# LCD_Sheet.net
KiCad netlist of a schematic drawn in Altium Designer
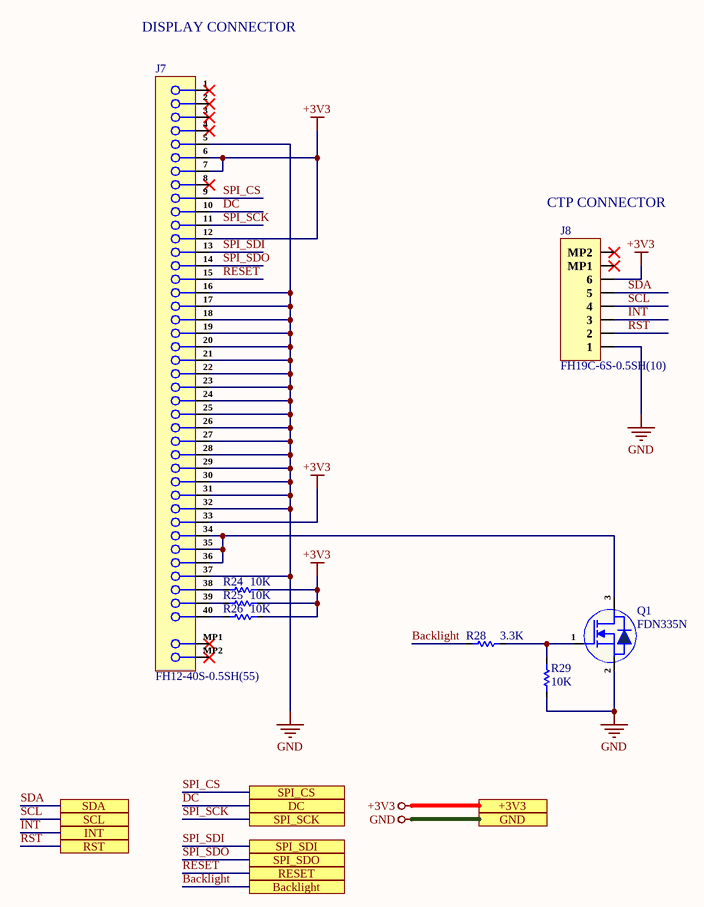
[diagram p0: LCD_Sheet.SchDoc]

(export (version "E")
  (design (tool "Eeschema 10.0.6"))
  (components
    (comp (ref "J7")
      (value "FH12-40S-0.5SH(55)")
      (footprint "FH12-40S-0.5SH(55)")
      (description "CONN FFC BOTTOM 40POS 0.50MM R/A")
      (fields (field (name "MANUFACTURER") "Hirose") (field (name "LCSC PART NUMBER") "C202114"))
      (libsource (lib "DigitalAzanClock") (part "FH12-40S-0.5SH(55)"))
    )
    (comp (ref "J8")
      (value "FH19C-6S-0.5SH(10)")
      (footprint "FH19C-6S-0.5SH(10)_")
      (description "CONN FFC BOTTOM 6POS 0.50MM R/A")
      (fields (field (name "MANUFACTURER") "Hirose") (field (name "LCSC PART NUMBER") "C424651"))
      (libsource (lib "DigitalAzanClock") (part "FH19C-6S-0.5SH(10)"))
    )
    (comp (ref "Q1")
      (value "FDN335N")
      (footprint "SOT-23")
      (description "SOT-23 MOSFETs ROHS")
      (fields (field (name "MANUFACTURER") "TECH PUBLIC") (field (name "LCSC PART NUMBER") "C5123904"))
      (libsource (lib "DigitalAzanClock") (part "FDN335N"))
    )
    (comp (ref "R24")
      (value "10K")
      (footprint "Res-0603")
      (description "RES SMD 10K OHM 0.1% 1/10W 0603")
      (fields
        (field (name "MANUFACTURER") "Yageo")
        (field (name "MANUFACTURER PART NUMBER") "RT0603BRD0710KL")
      )
      (libsource (lib "DigitalAzanClock") (part "RT0603BRD0710KL"))
    )
    (comp (ref "R25")
      (value "10K")
      (footprint "Res-0603")
      (description "RES SMD 10K OHM 0.1% 1/10W 0603")
      (fields
        (field (name "MANUFACTURER") "Yageo")
        (field (name "MANUFACTURER PART NUMBER") "RT0603BRD0710KL")
      )
      (libsource (lib "DigitalAzanClock") (part "RT0603BRD0710KL"))
    )
    (comp (ref "R26")
      (value "10K")
      (footprint "Res-0603")
      (description "RES SMD 10K OHM 0.1% 1/10W 0603")
      (fields
        (field (name "MANUFACTURER") "Yageo")
        (field (name "MANUFACTURER PART NUMBER") "RT0603BRD0710KL")
      )
      (libsource (lib "DigitalAzanClock") (part "RT0603BRD0710KL"))
    )
    (comp (ref "R28")
      (value "3.3K")
      (footprint "Res-0603")
      (description "RES SMD 3.3K OHM 1% 1/10W 0603")
      (fields
        (field (name "MANUFACTURER") "Yageo Phycomp")
        (field (name "MANUFACTURER PART NUMBER") "RC0603FR-073K3L")
      )
      (libsource (lib "DigitalAzanClock") (part "RC0603FR-073K3L"))
    )
    (comp (ref "R29")
      (value "10K")
      (footprint "Res-0603")
      (description "RES SMD 10K OHM 0.1% 1/10W 0603")
      (fields
        (field (name "MANUFACTURER") "Yageo")
        (field (name "MANUFACTURER PART NUMBER") "RT0603BRD0710KL")
      )
      (libsource (lib "DigitalAzanClock") (part "RT0603BRD0710KL"))
    )
  )
  (nets
    (net (code "1") (name "+3V3") (class "Default")
      (node (ref "J7") (pin "12") (pinfunction "12_12") (pintype "passive"))
      (node (ref "J7") (pin "33") (pinfunction "33_33") (pintype "passive"))
      (node (ref "J7") (pin "6") (pinfunction "6_6") (pintype "passive"))
      (node (ref "J7") (pin "7") (pinfunction "7_7") (pintype "passive"))
      (node (ref "J8") (pin "6") (pinfunction "6_6") (pintype "passive"))
      (node (ref "R24") (pin "2") (pinfunction "2_2") (pintype "passive"))
      (node (ref "R25") (pin "2") (pinfunction "2_2") (pintype "passive"))
      (node (ref "R26") (pin "2") (pinfunction "2_2") (pintype "passive"))
    )
    (net (code "2") (name "/Backlight") (class "Default")
      (node (ref "R28") (pin "1") (pinfunction "1_1") (pintype "passive"))
    )
    (net (code "3") (name "/DC") (class "Default")
      (node (ref "J7") (pin "10") (pinfunction "10_10") (pintype "passive"))
    )
    (net (code "4") (name "/INT") (class "Default")
      (node (ref "J8") (pin "3") (pinfunction "3_3") (pintype "passive"))
    )
    (net (code "5") (name "/RESET") (class "Default")
      (node (ref "J7") (pin "15") (pinfunction "15_15") (pintype "passive"))
    )
    (net (code "6") (name "/RST") (class "Default")
      (node (ref "J8") (pin "2") (pinfunction "2_2") (pintype "passive"))
    )
    (net (code "7") (name "/SCL") (class "Default")
      (node (ref "J8") (pin "4") (pinfunction "4_4") (pintype "passive"))
    )
    (net (code "8") (name "/SDA") (class "Default")
      (node (ref "J8") (pin "5") (pinfunction "5_5") (pintype "passive"))
    )
    (net (code "9") (name "/SPI_CS") (class "Default")
      (node (ref "J7") (pin "9") (pinfunction "9_9") (pintype "passive"))
    )
    (net (code "10") (name "/SPI_SCK") (class "Default")
      (node (ref "J7") (pin "11") (pinfunction "11_11") (pintype "passive"))
    )
    (net (code "11") (name "/SPI_SDI") (class "Default")
      (node (ref "J7") (pin "13") (pinfunction "13_13") (pintype "passive"))
    )
    (net (code "12") (name "/SPI_SDO") (class "Default")
      (node (ref "J7") (pin "14") (pinfunction "14_14") (pintype "passive"))
    )
    (net (code "13") (name "GND") (class "Default")
      (node (ref "J7") (pin "16") (pinfunction "16_16") (pintype "passive"))
      (node (ref "J7") (pin "17") (pinfunction "17_17") (pintype "passive"))
      (node (ref "J7") (pin "18") (pinfunction "18_18") (pintype "passive"))
      (node (ref "J7") (pin "19") (pinfunction "19_19") (pintype "passive"))
      (node (ref "J7") (pin "20") (pinfunction "20_20") (pintype "passive"))
      (node (ref "J7") (pin "21") (pinfunction "21_21") (pintype "passive"))
      (node (ref "J7") (pin "22") (pinfunction "22_22") (pintype "passive"))
      (node (ref "J7") (pin "23") (pinfunction "23_23") (pintype "passive"))
      (node (ref "J7") (pin "24") (pinfunction "24_24") (pintype "passive"))
      (node (ref "J7") (pin "25") (pinfunction "25_25") (pintype "passive"))
      (node (ref "J7") (pin "26") (pinfunction "26_26") (pintype "passive"))
      (node (ref "J7") (pin "27") (pinfunction "27_27") (pintype "passive"))
      (node (ref "J7") (pin "28") (pinfunction "28_28") (pintype "passive"))
      (node (ref "J7") (pin "29") (pinfunction "29_29") (pintype "passive"))
      (node (ref "J7") (pin "30") (pinfunction "30_30") (pintype "passive"))
      (node (ref "J7") (pin "31") (pinfunction "31_31") (pintype "passive"))
      (node (ref "J7") (pin "32") (pinfunction "32_32") (pintype "passive"))
      (node (ref "J7") (pin "37") (pinfunction "37_37") (pintype "passive"))
      (node (ref "J7") (pin "5") (pinfunction "5_5") (pintype "passive"))
      (node (ref "J8") (pin "1") (pinfunction "1_1") (pintype "passive"))
      (node (ref "Q1") (pin "2") (pinfunction "S_2") (pintype "passive"))
      (node (ref "R29") (pin "1") (pinfunction "1_1") (pintype "passive"))
    )
    (net (code "14") (name "Net-(J7-Pad38)") (class "Default")
      (node (ref "J7") (pin "38") (pinfunction "38_38") (pintype "passive"))
      (node (ref "R24") (pin "1") (pinfunction "1_1") (pintype "passive"))
    )
    (net (code "15") (name "Net-(J7-Pad39)") (class "Default")
      (node (ref "J7") (pin "39") (pinfunction "39_39") (pintype "passive"))
      (node (ref "R25") (pin "1") (pinfunction "1_1") (pintype "passive"))
    )
    (net (code "16") (name "Net-(J7-Pad40)") (class "Default")
      (node (ref "J7") (pin "40") (pinfunction "40_40") (pintype "passive"))
      (node (ref "R26") (pin "1") (pinfunction "1_1") (pintype "passive"))
    )
    (net (code "17") (name "Net-(Q1-D)") (class "Default")
      (node (ref "J7") (pin "34") (pinfunction "34_34") (pintype "passive"))
      (node (ref "J7") (pin "35") (pinfunction "35_35") (pintype "passive"))
      (node (ref "J7") (pin "36") (pinfunction "36_36") (pintype "passive"))
      (node (ref "Q1") (pin "3") (pinfunction "D_3") (pintype "passive"))
    )
    (net (code "18") (name "Net-(Q1-G)") (class "Default")
      (node (ref "Q1") (pin "1") (pinfunction "G_1") (pintype "passive"))
      (node (ref "R28") (pin "2") (pinfunction "2_2") (pintype "passive"))
      (node (ref "R29") (pin "2") (pinfunction "2_2") (pintype "passive"))
    )
    (net (code "19") (name "unconnected-(J7-Pad1)") (class "Default")
      (node (ref "J7") (pin "1") (pinfunction "1_1") (pintype "passive+no_connect"))
    )
    (net (code "20") (name "unconnected-(J7-Pad2)") (class "Default")
      (node (ref "J7") (pin "2") (pinfunction "2_2") (pintype "passive+no_connect"))
    )
    (net (code "21") (name "unconnected-(J7-Pad3)") (class "Default")
      (node (ref "J7") (pin "3") (pinfunction "3_3") (pintype "passive+no_connect"))
    )
    (net (code "22") (name "unconnected-(J7-Pad4)") (class "Default")
      (node (ref "J7") (pin "4") (pinfunction "4_4") (pintype "passive+no_connect"))
    )
    (net (code "23") (name "unconnected-(J7-Pad8)") (class "Default")
      (node (ref "J7") (pin "8") (pinfunction "8_8") (pintype "passive+no_connect"))
    )
    (net (code "24") (name "unconnected-(J7-PadMP1)") (class "Default")
      (node (ref "J7") (pin "MP1") (pinfunction "MP1_MP1") (pintype "passive+no_connect"))
    )
    (net (code "25") (name "unconnected-(J7-PadMP2)") (class "Default")
      (node (ref "J7") (pin "MP2") (pinfunction "MP2_MP2") (pintype "passive+no_connect"))
    )
    (net (code "26") (name "unconnected-(J8-PadMP1)") (class "Default")
      (node (ref "J8") (pin "MP1") (pinfunction "MP1_MP1") (pintype "passive+no_connect"))
    )
    (net (code "27") (name "unconnected-(J8-PadMP2)") (class "Default")
      (node (ref "J8") (pin "MP2") (pinfunction "MP2_MP2") (pintype "passive+no_connect"))
    )
  )
)
